# Sheet1.net
KiCad netlist of a schematic drawn in Altium Designer
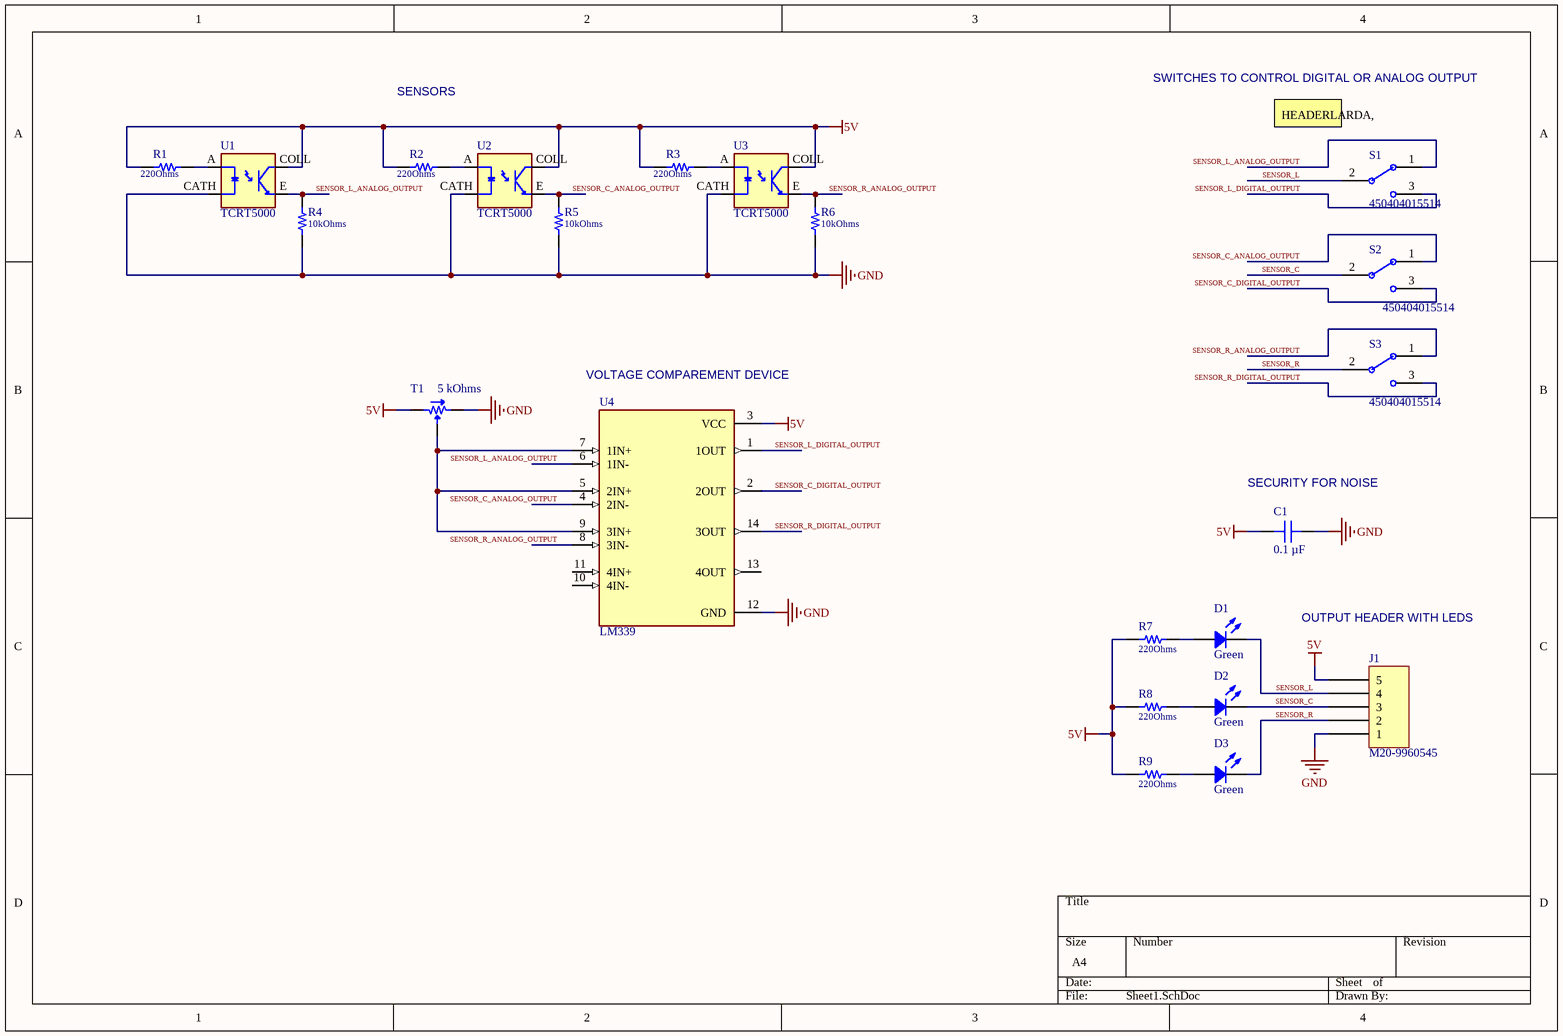
[diagram p0: Sheet1.SchDoc]

(export (version "E")
  (design (tool "Eeschema 10.0.6"))
  (components
    (comp (ref "C1")
      (value "0.1 µF")
      (footprint "CAP 0805_2012")
      (description "CAP CER 0.1UF 50V X7R 0805")
      (fields (field (name "PART NUMBER") "CC0805JRX7R9BB104") (field (name "MANUFACTURER") "Yageo"))
      (libsource (lib "Celestial Altium Library - altium_library") (part "Capacitor"))
    )
    (comp (ref "D1")
      (value "Green")
      (footprint "LED 0805_2012 GREEN")
      (description "2.0X1.2MM GREEN SMD 0805 LED")
      (fields (field (name "PART NUMBER") "XZVG54W-4") (field (name "MANUFACTURER") "SunLED"))
      (libsource (lib "Celestial Altium Library - altium_library") (part "LED"))
    )
    (comp (ref "D2")
      (value "Green")
      (footprint "LED 0805_2012 GREEN")
      (description "2.0X1.2MM GREEN SMD 0805 LED")
      (fields (field (name "PART NUMBER") "XZVG54W-4") (field (name "MANUFACTURER") "SunLED"))
      (libsource (lib "Celestial Altium Library - altium_library") (part "LED"))
    )
    (comp (ref "D3")
      (value "Green")
      (footprint "LED 0805_2012 GREEN")
      (description "2.0X1.2MM GREEN SMD 0805 LED")
      (fields (field (name "PART NUMBER") "XZVG54W-4") (field (name "MANUFACTURER") "SunLED"))
      (libsource (lib "Celestial Altium Library - altium_library") (part "LED"))
    )
    (comp (ref "J1")
      (value "M20-9960545")
      (footprint "HARWIN M20-9960545")
      (description "CONN HEADER R/A 5POS 2.54MM")
      (fields (field (name "MANUFACTURER") "Harwin Inc."))
      (libsource (lib "Celestial Altium Library - altium_library") (part "5 Pin"))
    )
    (comp (ref "R1")
      (value "220Ohms")
      (footprint "RES 0805_2012")
      (description "RES SMD 3K OHM 1% 1/8W 0805")
      (fields
        (field (name "PART NUMBER") "ERJ-6ENF3001V")
        (field (name "MANUFACTURER") "Panasonic Electronic Components")
      )
      (libsource (lib "Celestial Altium Library - altium_library") (part "Resistor"))
    )
    (comp (ref "R2")
      (value "220Ohms")
      (footprint "RES 0805_2012")
      (description "RES SMD 3K OHM 1% 1/8W 0805")
      (fields
        (field (name "PART NUMBER") "ERJ-6ENF3001V")
        (field (name "MANUFACTURER") "Panasonic Electronic Components")
      )
      (libsource (lib "Celestial Altium Library - altium_library") (part "Resistor"))
    )
    (comp (ref "R3")
      (value "220Ohms")
      (footprint "RES 0805_2012")
      (description "RES SMD 3K OHM 1% 1/8W 0805")
      (fields
        (field (name "PART NUMBER") "ERJ-6ENF3001V")
        (field (name "MANUFACTURER") "Panasonic Electronic Components")
      )
      (libsource (lib "Celestial Altium Library - altium_library") (part "Resistor"))
    )
    (comp (ref "R4")
      (value "10kOhms")
      (footprint "RES 0805_2012")
      (description "RES SMD 3K OHM 1% 1/8W 0805")
      (fields
        (field (name "PART NUMBER") "ERJ-6ENF3001V")
        (field (name "MANUFACTURER") "Panasonic Electronic Components")
      )
      (libsource (lib "Celestial Altium Library - altium_library") (part "Resistor"))
    )
    (comp (ref "R5")
      (value "10kOhms")
      (footprint "RES 0805_2012")
      (description "RES SMD 3K OHM 1% 1/8W 0805")
      (fields
        (field (name "PART NUMBER") "ERJ-6ENF3001V")
        (field (name "MANUFACTURER") "Panasonic Electronic Components")
      )
      (libsource (lib "Celestial Altium Library - altium_library") (part "Resistor"))
    )
    (comp (ref "R6")
      (value "10kOhms")
      (footprint "RES 0805_2012")
      (description "RES SMD 3K OHM 1% 1/8W 0805")
      (fields
        (field (name "PART NUMBER") "ERJ-6ENF3001V")
        (field (name "MANUFACTURER") "Panasonic Electronic Components")
      )
      (libsource (lib "Celestial Altium Library - altium_library") (part "Resistor"))
    )
    (comp (ref "R7")
      (value "220Ohms")
      (footprint "RES 0805_2012")
      (description "RES SMD 3K OHM 1% 1/8W 0805")
      (fields
        (field (name "PART NUMBER") "ERJ-6ENF3001V")
        (field (name "MANUFACTURER") "Panasonic Electronic Components")
      )
      (libsource (lib "Celestial Altium Library - altium_library") (part "Resistor"))
    )
    (comp (ref "R8")
      (value "220Ohms")
      (footprint "RES 0805_2012")
      (description "RES SMD 3K OHM 1% 1/8W 0805")
      (fields
        (field (name "PART NUMBER") "ERJ-6ENF3001V")
        (field (name "MANUFACTURER") "Panasonic Electronic Components")
      )
      (libsource (lib "Celestial Altium Library - altium_library") (part "Resistor"))
    )
    (comp (ref "R9")
      (value "220Ohms")
      (footprint "RES 0805_2012")
      (description "RES SMD 3K OHM 1% 1/8W 0805")
      (fields
        (field (name "PART NUMBER") "ERJ-6ENF3001V")
        (field (name "MANUFACTURER") "Panasonic Electronic Components")
      )
      (libsource (lib "Celestial Altium Library - altium_library") (part "Resistor"))
    )
    (comp (ref "S1")
      (value "450404015514")
      (footprint "WURTH WS-SLSU 450404015514")
      (description "MINI SLIDE SWITCH 6.7 X 2.7 MM.")
      (fields (field (name "MANUFACTURER") "Würth Elektronik") (field (name "PUBLISHER") "Wurth Elektronik"))
      (libsource (lib "Celestial Altium Library - altium_library") (part "WURTH WS-SLSU 450404015514"))
    )
    (comp (ref "S2")
      (value "450404015514")
      (footprint "WURTH WS-SLSU 450404015514")
      (description "MINI SLIDE SWITCH 6.7 X 2.7 MM.")
      (fields (field (name "MANUFACTURER") "Würth Elektronik") (field (name "PUBLISHER") "Wurth Elektronik"))
      (libsource (lib "Celestial Altium Library - altium_library") (part "WURTH WS-SLSU 450404015514"))
    )
    (comp (ref "S3")
      (value "450404015514")
      (footprint "WURTH WS-SLSU 450404015514")
      (description "MINI SLIDE SWITCH 6.7 X 2.7 MM.")
      (fields (field (name "MANUFACTURER") "Würth Elektronik") (field (name "PUBLISHER") "Wurth Elektronik"))
      (libsource (lib "Celestial Altium Library - altium_library") (part "WURTH WS-SLSU 450404015514"))
    )
    (comp (ref "T1")
      (value "5 kOhms")
      (footprint "POT BOURNS TRIMPOT TC33")
      (description "TRIMMER 5K OHM 0.1W J LEAD TOP")
      (fields (field (name "PART NUMBER") "TC33X-2-502E") (field (name "MANUFACTURER") "Bourns Inc."))
      (libsource (lib "Celestial Altium Library - altium_library") (part "Potentiometer"))
    )
    (comp (ref "U1")
      (value "TCRT5000")
      (footprint "PcbLib1:OPTO_TCRT5000")
      (description "950 nm 60 mA Through Hole Reflective Optical Sensor with Transistor Output")
      (libsource (lib "Schlib1") (part "TCRT5000"))
    )
    (comp (ref "U2")
      (value "TCRT5000")
      (footprint "PcbLib1:OPTO_TCRT5000")
      (description "950 nm 60 mA Through Hole Reflective Optical Sensor with Transistor Output")
      (libsource (lib "Schlib1") (part "TCRT5000"))
    )
    (comp (ref "U3")
      (value "TCRT5000")
      (footprint "PcbLib1:OPTO_TCRT5000")
      (description "950 nm 60 mA Through Hole Reflective Optical Sensor with Transistor Output")
      (libsource (lib "Schlib1") (part "TCRT5000"))
    )
    (comp (ref "U4")
      (value "LM339")
      (footprint "PcbLib1:SOIC127P600X175-14N")
      (fields (field (name "MF") "Texas Instruments"))
      (libsource (lib "Schlib1") (part "LM339"))
    )
  )
  (nets
    (net (code "1") (name "/SENSOR_C") (class "Default")
      (node (ref "D2") (pin "2") (pinfunction "2_2") (pintype "passive"))
      (node (ref "J1") (pin "3") (pinfunction "3_3") (pintype "passive"))
      (node (ref "S2") (pin "2") (pinfunction "COM_2") (pintype "passive"))
    )
    (net (code "2") (name "/SENSOR_C_ANALOG_OUTPUT") (class "Default")
      (node (ref "R5") (pin "1") (pinfunction "1_1") (pintype "passive"))
      (node (ref "S2") (pin "1") (pinfunction "1_1") (pintype "passive"))
      (node (ref "U2") (pin "E") (pinfunction "E_E") (pintype "passive"))
      (node (ref "U4") (pin "4") (pinfunction "2IN-_4") (pintype "input"))
    )
    (net (code "3") (name "/SENSOR_C_DIGITAL_OUTPUT") (class "Default")
      (node (ref "S2") (pin "3") (pinfunction "3_3") (pintype "passive"))
      (node (ref "U4") (pin "2") (pinfunction "2OUT_2") (pintype "output"))
    )
    (net (code "4") (name "/SENSOR_L") (class "Default")
      (node (ref "D1") (pin "2") (pinfunction "2_2") (pintype "passive"))
      (node (ref "J1") (pin "4") (pinfunction "4_4") (pintype "passive"))
      (node (ref "S1") (pin "2") (pinfunction "COM_2") (pintype "passive"))
    )
    (net (code "5") (name "/SENSOR_L_ANALOG_OUTPUT") (class "Default")
      (node (ref "R4") (pin "1") (pinfunction "1_1") (pintype "passive"))
      (node (ref "S1") (pin "1") (pinfunction "1_1") (pintype "passive"))
      (node (ref "U1") (pin "E") (pinfunction "E_E") (pintype "passive"))
      (node (ref "U4") (pin "6") (pinfunction "1IN-_6") (pintype "input"))
    )
    (net (code "6") (name "/SENSOR_L_DIGITAL_OUTPUT") (class "Default")
      (node (ref "S1") (pin "3") (pinfunction "3_3") (pintype "passive"))
      (node (ref "U4") (pin "1") (pinfunction "1OUT_1") (pintype "output"))
    )
    (net (code "7") (name "/SENSOR_R") (class "Default")
      (node (ref "D3") (pin "2") (pinfunction "2_2") (pintype "passive"))
      (node (ref "J1") (pin "2") (pinfunction "2_2") (pintype "passive"))
      (node (ref "S3") (pin "2") (pinfunction "COM_2") (pintype "passive"))
    )
    (net (code "8") (name "/SENSOR_R_ANALOG_OUTPUT") (class "Default")
      (node (ref "R6") (pin "1") (pinfunction "1_1") (pintype "passive"))
      (node (ref "S3") (pin "1") (pinfunction "1_1") (pintype "passive"))
      (node (ref "U3") (pin "E") (pinfunction "E_E") (pintype "passive"))
      (node (ref "U4") (pin "8") (pinfunction "3IN-_8") (pintype "input"))
    )
    (net (code "9") (name "/SENSOR_R_DIGITAL_OUTPUT") (class "Default")
      (node (ref "S3") (pin "3") (pinfunction "3_3") (pintype "passive"))
      (node (ref "U4") (pin "14") (pinfunction "3OUT_14") (pintype "output"))
    )
    (net (code "10") (name "5V") (class "Default")
      (node (ref "C1") (pin "2") (pinfunction "2_2") (pintype "passive"))
      (node (ref "J1") (pin "5") (pinfunction "5_5") (pintype "passive"))
      (node (ref "R1") (pin "1") (pinfunction "1_1") (pintype "passive"))
      (node (ref "R2") (pin "1") (pinfunction "1_1") (pintype "passive"))
      (node (ref "R3") (pin "1") (pinfunction "1_1") (pintype "passive"))
      (node (ref "R7") (pin "2") (pinfunction "2_2") (pintype "passive"))
      (node (ref "R8") (pin "2") (pinfunction "2_2") (pintype "passive"))
      (node (ref "R9") (pin "2") (pinfunction "2_2") (pintype "passive"))
      (node (ref "T1") (pin "1") (pinfunction "1_1") (pintype "passive"))
      (node (ref "U1") (pin "COLL") (pinfunction "COLL_COLL") (pintype "passive"))
      (node (ref "U2") (pin "COLL") (pinfunction "COLL_COLL") (pintype "passive"))
      (node (ref "U3") (pin "COLL") (pinfunction "COLL_COLL") (pintype "passive"))
      (node (ref "U4") (pin "3") (pinfunction "VCC_3") (pintype "power_in"))
    )
    (net (code "11") (name "GND") (class "Default")
      (node (ref "C1") (pin "1") (pinfunction "1_1") (pintype "passive"))
      (node (ref "J1") (pin "1") (pinfunction "1_1") (pintype "passive"))
      (node (ref "R4") (pin "2") (pinfunction "2_2") (pintype "passive"))
      (node (ref "R5") (pin "2") (pinfunction "2_2") (pintype "passive"))
      (node (ref "R6") (pin "2") (pinfunction "2_2") (pintype "passive"))
      (node (ref "T1") (pin "3") (pinfunction "3_3") (pintype "passive"))
      (node (ref "U1") (pin "CATH") (pinfunction "CATH_CATH") (pintype "passive"))
      (node (ref "U2") (pin "CATH") (pinfunction "CATH_CATH") (pintype "passive"))
      (node (ref "U3") (pin "CATH") (pinfunction "CATH_CATH") (pintype "passive"))
      (node (ref "U4") (pin "12") (pinfunction "GND_12") (pintype "power_in"))
    )
    (net (code "12") (name "Net-(D1-Pad1)") (class "Default")
      (node (ref "D1") (pin "1") (pinfunction "1_1") (pintype "passive"))
      (node (ref "R7") (pin "1") (pinfunction "1_1") (pintype "passive"))
    )
    (net (code "13") (name "Net-(D2-Pad1)") (class "Default")
      (node (ref "D2") (pin "1") (pinfunction "1_1") (pintype "passive"))
      (node (ref "R8") (pin "1") (pinfunction "1_1") (pintype "passive"))
    )
    (net (code "14") (name "Net-(D3-Pad1)") (class "Default")
      (node (ref "D3") (pin "1") (pinfunction "1_1") (pintype "passive"))
      (node (ref "R9") (pin "1") (pinfunction "1_1") (pintype "passive"))
    )
    (net (code "15") (name "Net-(R1-Pad2)") (class "Default")
      (node (ref "R1") (pin "2") (pinfunction "2_2") (pintype "passive"))
      (node (ref "U1") (pin "A") (pinfunction "A_A") (pintype "passive"))
    )
    (net (code "16") (name "Net-(R2-Pad2)") (class "Default")
      (node (ref "R2") (pin "2") (pinfunction "2_2") (pintype "passive"))
      (node (ref "U2") (pin "A") (pinfunction "A_A") (pintype "passive"))
    )
    (net (code "17") (name "Net-(R3-Pad2)") (class "Default")
      (node (ref "R3") (pin "2") (pinfunction "2_2") (pintype "passive"))
      (node (ref "U3") (pin "A") (pinfunction "A_A") (pintype "passive"))
    )
    (net (code "18") (name "Net-(U4-1IN+)") (class "Default")
      (node (ref "T1") (pin "2") (pinfunction "2_2") (pintype "passive"))
      (node (ref "U4") (pin "5") (pinfunction "2IN+_5") (pintype "input"))
      (node (ref "U4") (pin "7") (pinfunction "1IN+_7") (pintype "input"))
      (node (ref "U4") (pin "9") (pinfunction "3IN+_9") (pintype "input"))
    )
    (net (code "19") (name "unconnected-(U4-4IN+-Pad11)") (class "Default")
      (node (ref "U4") (pin "11") (pinfunction "4IN+_11") (pintype "input"))
    )
    (net (code "20") (name "unconnected-(U4-4IN--Pad10)") (class "Default")
      (node (ref "U4") (pin "10") (pinfunction "4IN-_10") (pintype "input"))
    )
    (net (code "21") (name "unconnected-(U4-4OUT-Pad13)") (class "Default")
      (node (ref "U4") (pin "13") (pinfunction "4OUT_13") (pintype "output"))
    )
  )
)
